# receiver.net
KiCad netlist of a schematic drawn in EAGLE
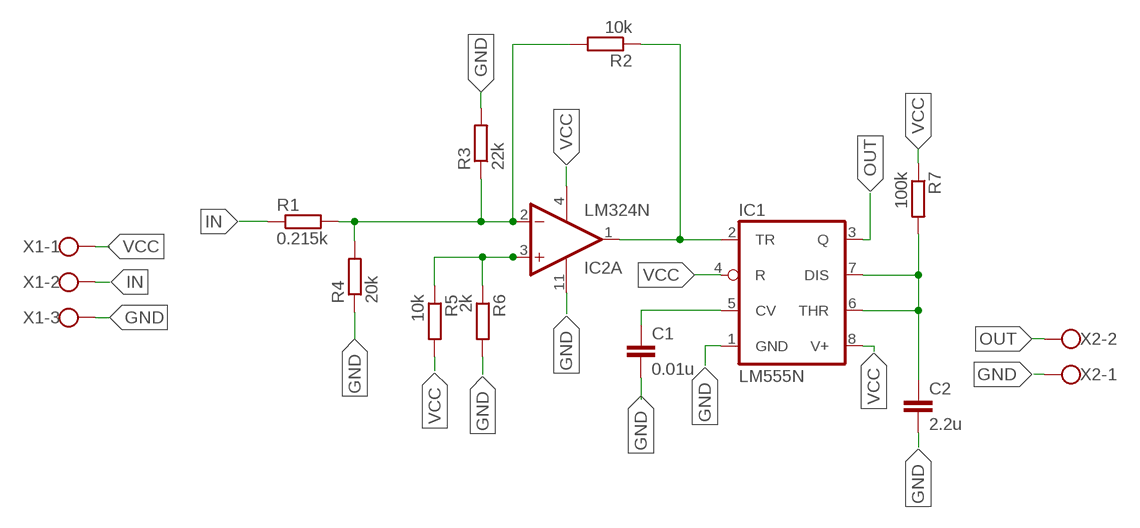
[diagram p0: schematic, sheet 1]

(export (version "E")
  (design (tool "Eeschema 10.0.6"))
  (components
    (comp (ref "C1")
      (value "0.01u")
      (footprint "eagle-import:C050-025X075")
      (libsource (lib "eagle-import") (part "C-EU050-025X075"))
    )
    (comp (ref "C2")
      (value "2.2u")
      (footprint "eagle-import:C050-025X075")
      (libsource (lib "eagle-import") (part "C-EU050-025X075"))
    )
    (comp (ref "IC1")
      (value "LM555N")
      (footprint "eagle-import:DIL08")
      (libsource (lib "eagle-import") (part "555NLM"))
    )
    (comp (ref "IC2")
      (value "LM324N")
      (footprint "eagle-import:DIL14")
      (libsource (lib "eagle-import") (part "LM324N"))
    )
    (comp (ref "R1")
      (value "0.215k")
      (footprint "eagle-import:0207_10")
      (libsource (lib "eagle-import") (part "R-EU_0207/10"))
    )
    (comp (ref "R2")
      (value "10k")
      (footprint "eagle-import:0207_10")
      (libsource (lib "eagle-import") (part "R-EU_0207/10"))
    )
    (comp (ref "R3")
      (value "22k")
      (footprint "eagle-import:0207_10")
      (libsource (lib "eagle-import") (part "R-EU_0207/10"))
    )
    (comp (ref "R4")
      (value "20k")
      (footprint "eagle-import:0207_10")
      (libsource (lib "eagle-import") (part "R-EU_0207/10"))
    )
    (comp (ref "R5")
      (value "10k")
      (footprint "eagle-import:0207_10")
      (libsource (lib "eagle-import") (part "R-EU_0207/10"))
    )
    (comp (ref "R6")
      (value "2k")
      (footprint "eagle-import:0207_10")
      (libsource (lib "eagle-import") (part "R-EU_0207/10"))
    )
    (comp (ref "R7")
      (value "100k")
      (footprint "eagle-import:0207_10")
      (libsource (lib "eagle-import") (part "R-EU_0207/10"))
    )
    (comp (ref "X1")
      (value "W237-103")
      (footprint "eagle-import:W237-103")
      (fields (field (name "MPN") "237-103"))
      (libsource (lib "eagle-import") (part "W237-103"))
    )
    (comp (ref "X2")
      (value "W237-102")
      (footprint "eagle-import:W237-102")
      (fields (field (name "MPN") "237-102"))
      (libsource (lib "eagle-import") (part "W237-102"))
    )
  )
  (nets
    (net (code "1") (name "GND") (class "Default")
      (node (ref "C1") (pin "2") (pinfunction "2_2") (pintype "passive"))
      (node (ref "C2") (pin "2") (pinfunction "2_2") (pintype "passive"))
      (node (ref "IC1") (pin "1") (pinfunction "GND_1") (pintype "power_in"))
      (node (ref "IC2") (pin "11") (pinfunction "V-_11") (pintype "power_in"))
      (node (ref "R3") (pin "2") (pinfunction "2_2") (pintype "passive"))
      (node (ref "R4") (pin "1") (pinfunction "1_1") (pintype "passive"))
      (node (ref "R6") (pin "2") (pinfunction "2_2") (pintype "passive"))
      (node (ref "X1") (pin "3") (pinfunction "KL_3") (pintype "passive"))
      (node (ref "X2") (pin "1") (pinfunction "KL_1") (pintype "passive"))
    )
    (net (code "2") (name "IN") (class "Default")
      (node (ref "R1") (pin "1") (pinfunction "1_1") (pintype "passive"))
      (node (ref "X1") (pin "2") (pinfunction "KL_2") (pintype "passive"))
    )
    (net (code "3") (name "Net-(IC1-CV)") (class "Default")
      (node (ref "C1") (pin "1") (pinfunction "1_1") (pintype "passive"))
      (node (ref "IC1") (pin "5") (pinfunction "CV_5") (pintype "input"))
    )
    (net (code "4") (name "Net-(IC1-DIS)") (class "Default")
      (node (ref "C2") (pin "1") (pinfunction "1_1") (pintype "passive"))
      (node (ref "IC1") (pin "6") (pinfunction "THR_6") (pintype "input"))
      (node (ref "IC1") (pin "7") (pinfunction "DIS_7") (pintype "input"))
      (node (ref "R7") (pin "2") (pinfunction "2_2") (pintype "passive"))
    )
    (net (code "5") (name "Net-(IC1-TR)") (class "Default")
      (node (ref "IC1") (pin "2") (pinfunction "TR_2") (pintype "input"))
      (node (ref "IC2") (pin "1") (pinfunction "OUT_1") (pintype "output"))
      (node (ref "R2") (pin "1") (pinfunction "1_1") (pintype "passive"))
    )
    (net (code "6") (name "Net-(IC2A-+IN)") (class "Default")
      (node (ref "IC2") (pin "3") (pinfunction "+IN_3") (pintype "input"))
      (node (ref "R5") (pin "1") (pinfunction "1_1") (pintype "passive"))
      (node (ref "R6") (pin "1") (pinfunction "1_1") (pintype "passive"))
    )
    (net (code "7") (name "Net-(IC2A--IN)") (class "Default")
      (node (ref "IC2") (pin "2") (pinfunction "-IN_2") (pintype "input"))
      (node (ref "R1") (pin "2") (pinfunction "2_2") (pintype "passive"))
      (node (ref "R2") (pin "2") (pinfunction "2_2") (pintype "passive"))
      (node (ref "R3") (pin "1") (pinfunction "1_1") (pintype "passive"))
      (node (ref "R4") (pin "2") (pinfunction "2_2") (pintype "passive"))
    )
    (net (code "8") (name "OUT") (class "Default")
      (node (ref "IC1") (pin "3") (pinfunction "Q_3") (pintype "output"))
      (node (ref "X2") (pin "2") (pinfunction "KL_2") (pintype "passive"))
    )
    (net (code "9") (name "VCC") (class "Default")
      (node (ref "IC1") (pin "4") (pinfunction "R_4") (pintype "input"))
      (node (ref "IC1") (pin "8") (pinfunction "V+_8") (pintype "power_in"))
      (node (ref "IC2") (pin "4") (pinfunction "V+_4") (pintype "power_in"))
      (node (ref "R5") (pin "2") (pinfunction "2_2") (pintype "passive"))
      (node (ref "R7") (pin "1") (pinfunction "1_1") (pintype "passive"))
      (node (ref "X1") (pin "1") (pinfunction "KL_1") (pintype "passive"))
    )
  )
)
